# MCU_STM32F407ZGT6.net
KiCad netlist of a schematic drawn in Altium Designer
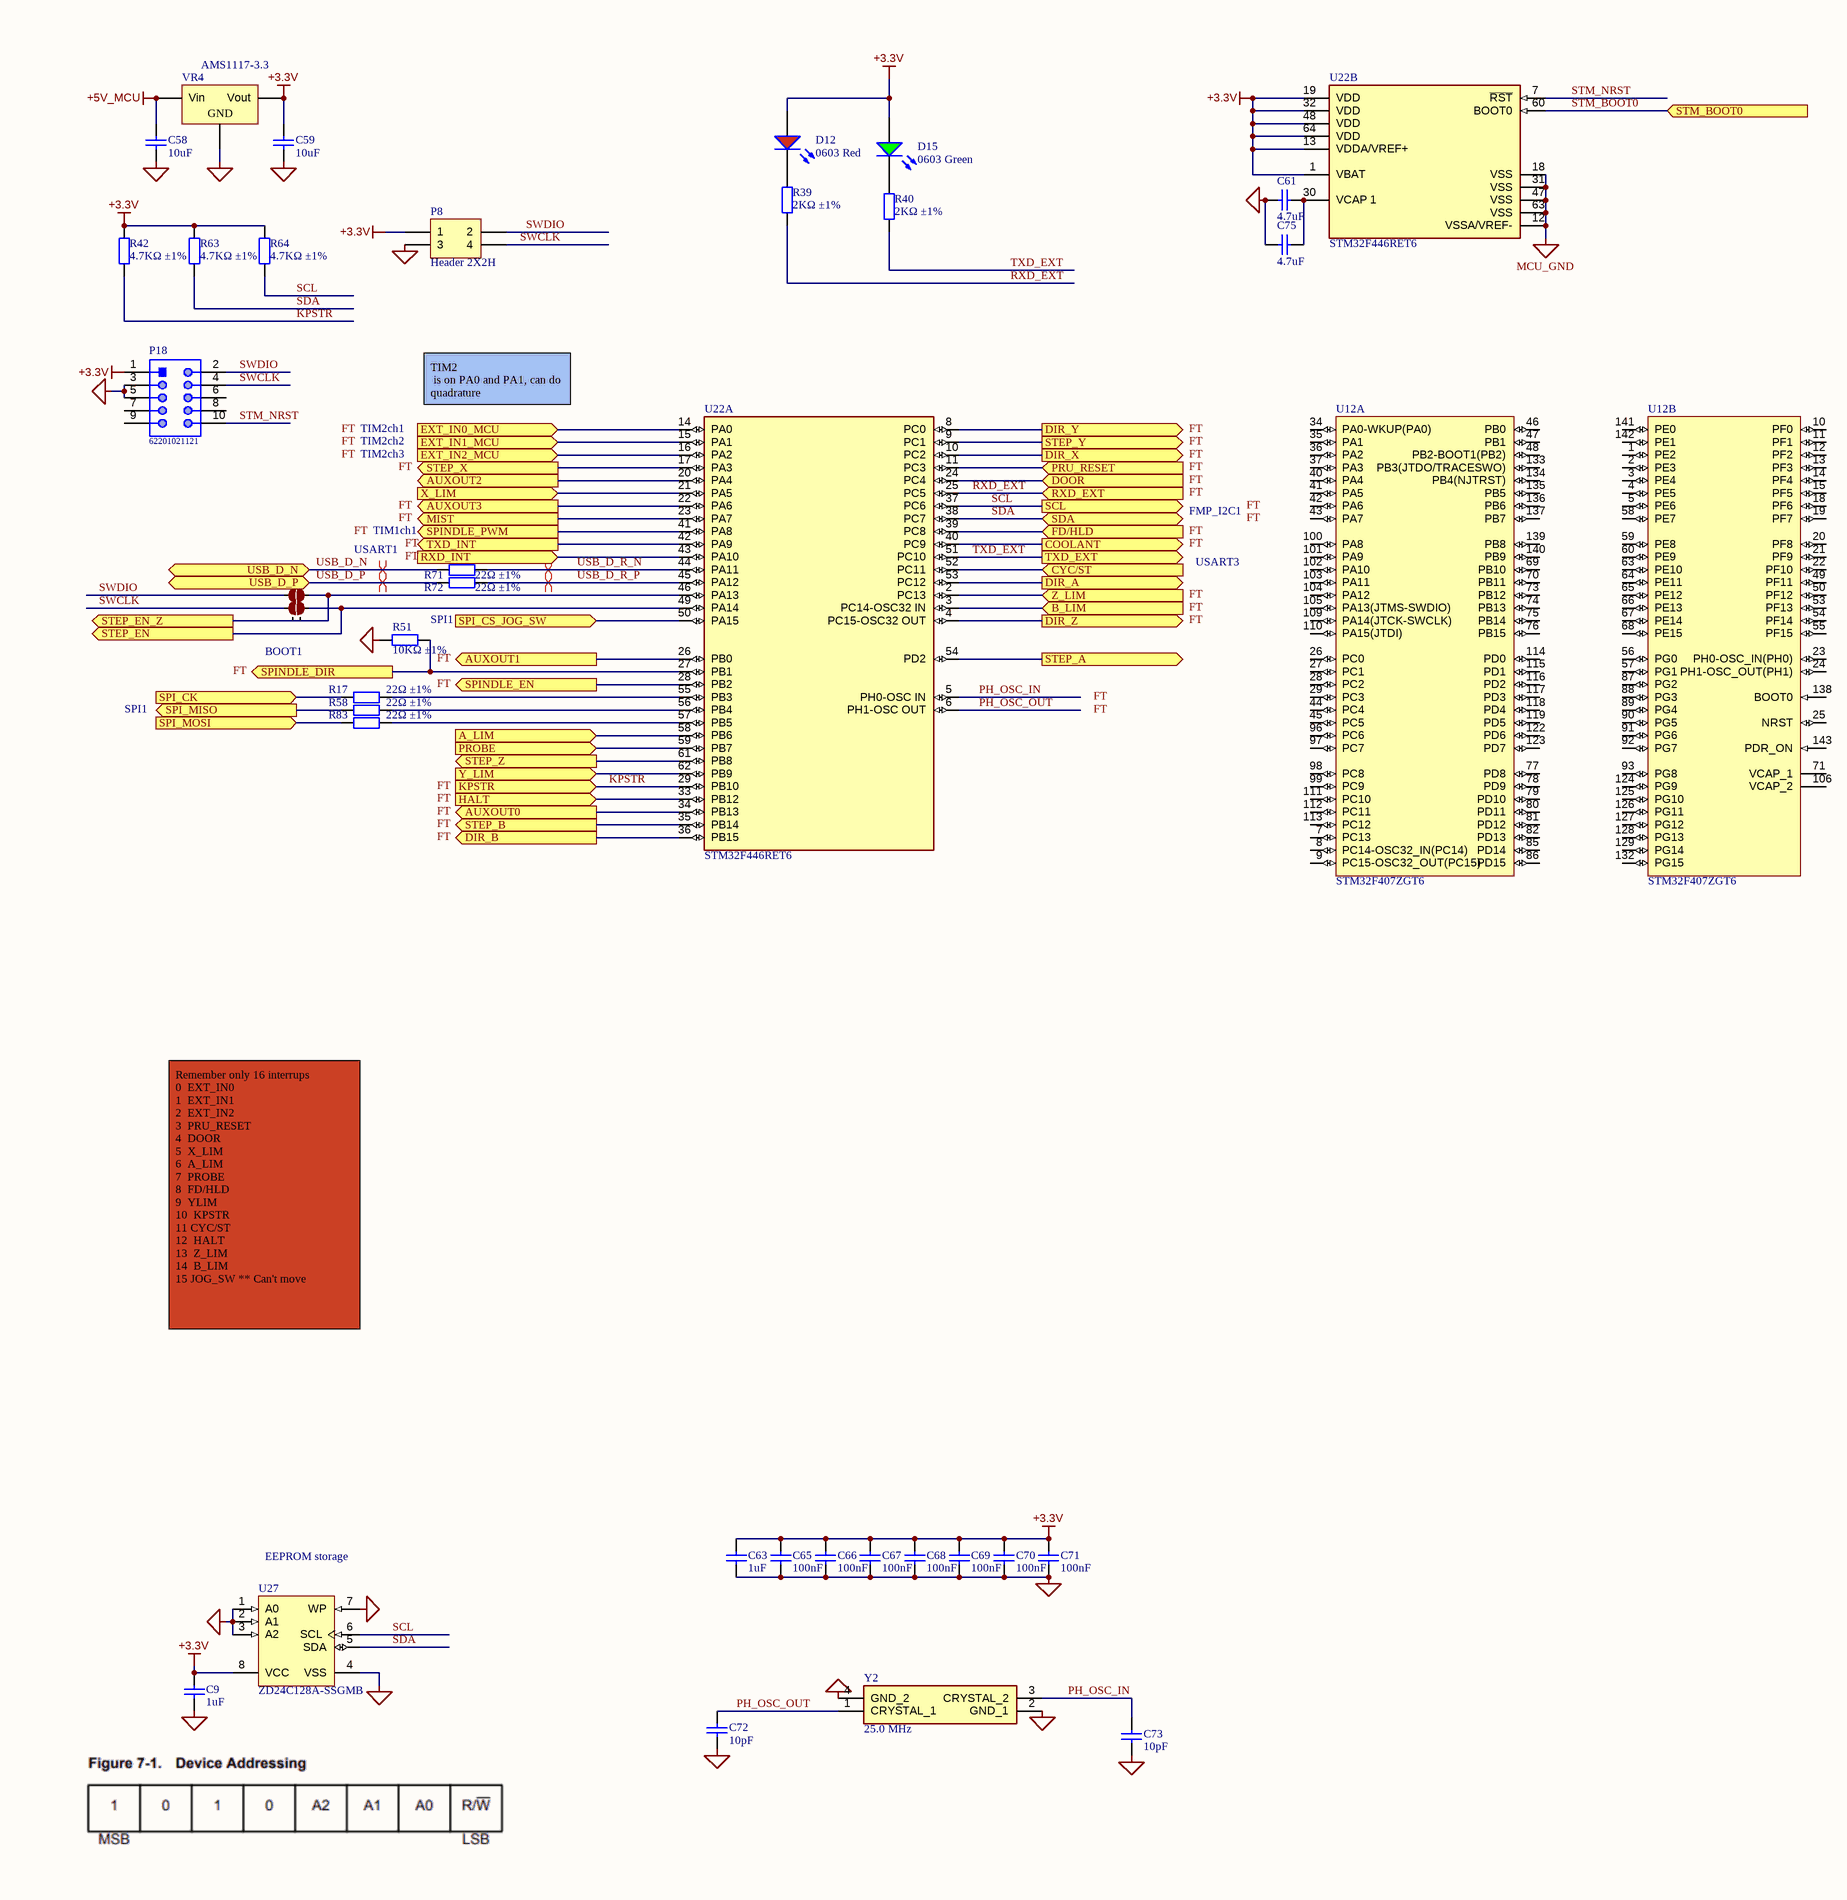
[diagram p0: MCU_STM32F407ZGT6.SchDoc, left]
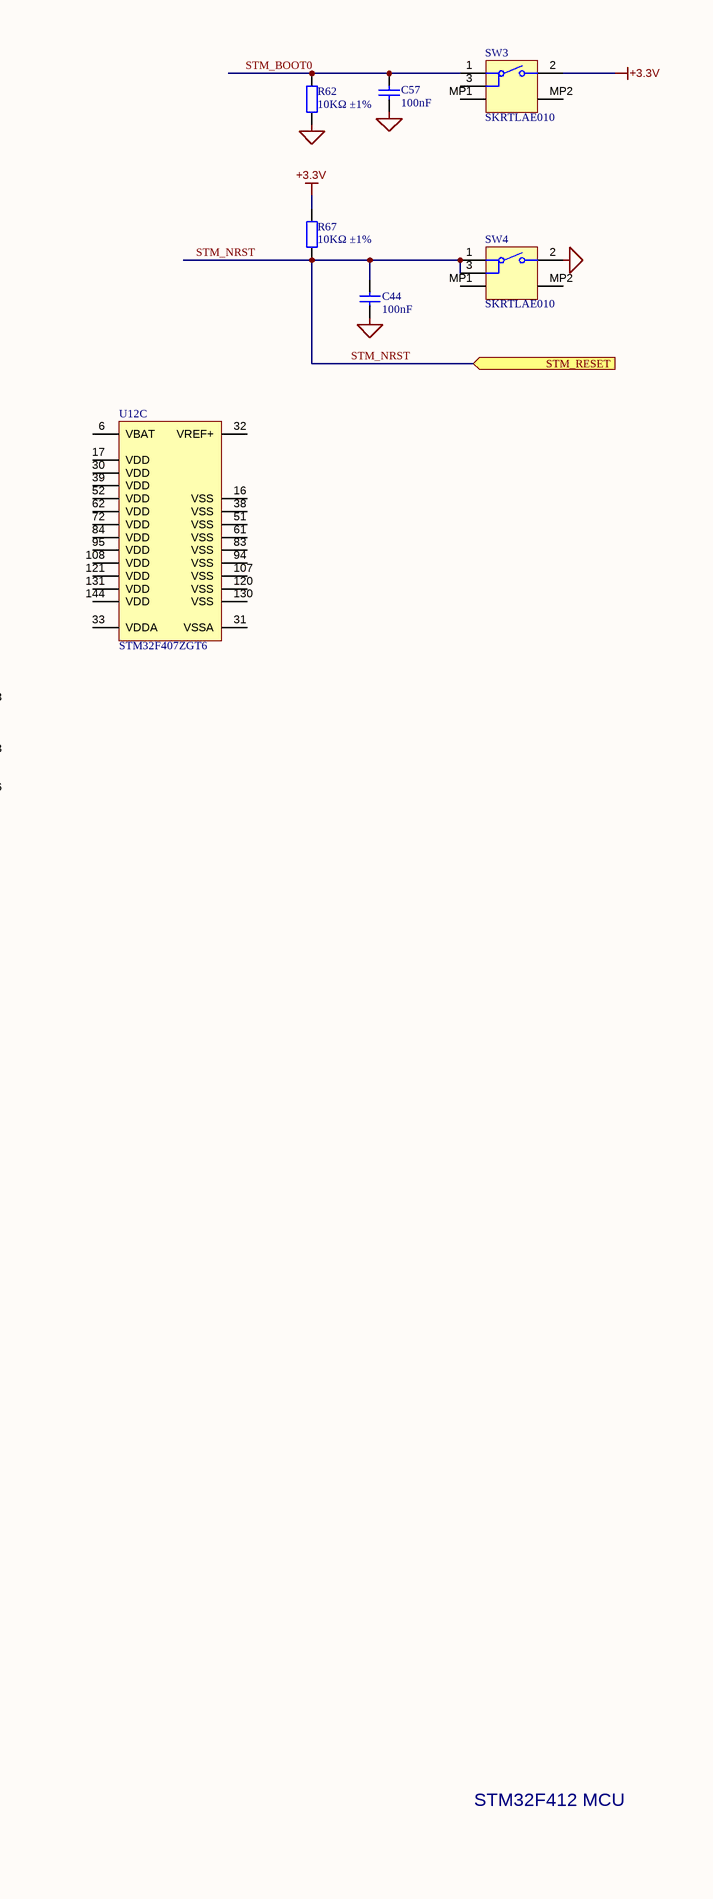
[diagram p1: MCU_STM32F407ZGT6.SchDoc, right]

(export (version "E")
  (design (tool "Eeschema 10.0.6"))
  (components
    (comp (ref "C9")
      (value "1uF")
      (footprint "0603_C")
      (description "Chip capacitors")
      (fields
        (field (name "MANUFACTURER") "Samsung Electro-Mechanics")
        (field (name "PARTNUMBER") "CL10A105KB8NNNC")
      )
      (libsource (lib "Cap") (part "0603 1uF (105) 10% 50V"))
    )
    (comp (ref "C44")
      (value "100nF")
      (footprint "0603_C")
      (description "Chip capacitors")
      (fields (field (name "MANUFACTURER") "YAGEO") (field (name "PARTNUMBER") "CC0603KRX7R9BB104"))
      (libsource (lib "Cap") (part "0603 100nF (104) 10% 50V"))
    )
    (comp (ref "C57")
      (value "100nF")
      (footprint "0603_C")
      (description "Chip capacitors")
      (fields (field (name "MANUFACTURER") "YAGEO") (field (name "PARTNUMBER") "CC0603KRX7R9BB104"))
      (libsource (lib "Cap") (part "0603 100nF (104) 10% 50V"))
    )
    (comp (ref "C58")
      (value "10uF")
      (footprint "1206_C")
      (description "Chip capacitors")
      (fields
        (field (name "MANUFACTURER") "Samsung Electro-Mechanics")
        (field (name "PARTNUMBER") "CL31A106KBHNNNE")
      )
      (libsource (lib "Cap") (part "1206 10uF (106) 10% 50V"))
    )
    (comp (ref "C59")
      (value "10uF")
      (footprint "1206_C")
      (description "Chip capacitors")
      (fields
        (field (name "MANUFACTURER") "Samsung Electro-Mechanics")
        (field (name "PARTNUMBER") "CL31A106KBHNNNE")
      )
      (libsource (lib "Cap") (part "1206 10uF (106) 10% 50V"))
    )
    (comp (ref "C61")
      (value "4.7uF")
      (footprint "0603_C")
      (description "Chip capacitors")
      (fields
        (field (name "MANUFACTURER") "Samsung Electro-Mechanics")
        (field (name "PARTNUMBER") "CL10A475KO8NNNC")
      )
      (libsource (lib "Cap") (part "0603 4.7uF (475) 10% 16V"))
    )
    (comp (ref "C63")
      (value "1uF")
      (footprint "0603_C")
      (description "Chip capacitors")
      (fields
        (field (name "MANUFACTURER") "Samsung Electro-Mechanics")
        (field (name "PARTNUMBER") "CL10A105KB8NNNC")
      )
      (libsource (lib "Cap") (part "0603 1uF (105) 10% 50V"))
    )
    (comp (ref "C65")
      (value "100nF")
      (footprint "0603_C")
      (description "Chip capacitors")
      (fields (field (name "MANUFACTURER") "YAGEO") (field (name "PARTNUMBER") "CC0603KRX7R9BB104"))
      (libsource (lib "Cap") (part "0603 100nF (104) 10% 50V"))
    )
    (comp (ref "C66")
      (value "100nF")
      (footprint "0603_C")
      (description "Chip capacitors")
      (fields (field (name "MANUFACTURER") "YAGEO") (field (name "PARTNUMBER") "CC0603KRX7R9BB104"))
      (libsource (lib "Cap") (part "0603 100nF (104) 10% 50V"))
    )
    (comp (ref "C67")
      (value "100nF")
      (footprint "0603_C")
      (description "Chip capacitors")
      (fields (field (name "MANUFACTURER") "YAGEO") (field (name "PARTNUMBER") "CC0603KRX7R9BB104"))
      (libsource (lib "Cap") (part "0603 100nF (104) 10% 50V"))
    )
    (comp (ref "C68")
      (value "100nF")
      (footprint "0603_C")
      (description "Chip capacitors")
      (fields (field (name "MANUFACTURER") "YAGEO") (field (name "PARTNUMBER") "CC0603KRX7R9BB104"))
      (libsource (lib "Cap") (part "0603 100nF (104) 10% 50V"))
    )
    (comp (ref "C69")
      (value "100nF")
      (footprint "0603_C")
      (description "Chip capacitors")
      (fields (field (name "MANUFACTURER") "YAGEO") (field (name "PARTNUMBER") "CC0603KRX7R9BB104"))
      (libsource (lib "Cap") (part "0603 100nF (104) 10% 50V"))
    )
    (comp (ref "C70")
      (value "100nF")
      (footprint "0603_C")
      (description "Chip capacitors")
      (fields (field (name "MANUFACTURER") "YAGEO") (field (name "PARTNUMBER") "CC0603KRX7R9BB104"))
      (libsource (lib "Cap") (part "0603 100nF (104) 10% 50V"))
    )
    (comp (ref "C71")
      (value "100nF")
      (footprint "0603_C")
      (description "Chip capacitors")
      (fields (field (name "MANUFACTURER") "YAGEO") (field (name "PARTNUMBER") "CC0603KRX7R9BB104"))
      (libsource (lib "Cap") (part "0603 100nF (104) 10% 50V"))
    )
    (comp (ref "C72")
      (value "10pF")
      (footprint "0603_C")
      (description "Chip capacitors")
      (fields
        (field (name "MANUFACTURER") "Samsung Electro-Mechanics")
        (field (name "PARTNUMBER") "CL10C100JB8NNNC")
      )
      (libsource (lib "Cap") (part "0603 10pF (100) 5% 50V"))
    )
    (comp (ref "C73")
      (value "10pF")
      (footprint "0603_C")
      (description "Chip capacitors")
      (fields
        (field (name "MANUFACTURER") "Samsung Electro-Mechanics")
        (field (name "PARTNUMBER") "CL10C100JB8NNNC")
      )
      (libsource (lib "Cap") (part "0603 10pF (100) 5% 50V"))
    )
    (comp (ref "C75")
      (value "4.7uF")
      (footprint "0603_C")
      (description "Chip capacitors")
      (fields
        (field (name "MANUFACTURER") "Samsung Electro-Mechanics")
        (field (name "PARTNUMBER") "CL10A475KO8NNNC")
      )
      (libsource (lib "Cap") (part "0603 4.7uF (475) 10% 16V"))
    )
    (comp (ref "D12")
      (value "0603 Red")
      (footprint "0603_LED_S1")
      (description "LED")
      (libsource (lib "LED") (part "0603 LED Red"))
    )
    (comp (ref "D15")
      (value "0603 Green")
      (footprint "0603_LED_S1")
      (description "LED")
      (libsource (lib "LED") (part "0603 LED Green"))
    )
    (comp (ref "J10")
      (value "2 way net solder junction - Normally Open")
      (footprint "2waySolder_NO")
      (libsource (lib "PrintNC_GRBLHAL_Breakout") (part "2waySolderNO"))
    )
    (comp (ref "J11")
      (value "2 way net solder junction - Normally Open")
      (footprint "2waySolder_NO")
      (libsource (lib "PrintNC_GRBLHAL_Breakout") (part "2waySolderNO"))
    )
    (comp (ref "P8")
      (value "Header 2X2H")
      (footprint "HDR2X2H")
      (description "Header, 2-Pin, Dual row, Right Angle")
      (fields (field (name "PUBLISHER") "Altium Limited"))
      (libsource (lib "Miscellaneous Connectors") (part "Header 2X2H"))
    )
    (comp (ref "P18")
      (value "62201021121")
      (footprint "62201021121")
      (description "THT Vertical Pin Header WR-PHD, Pitch 1.27 mm, Dual Row, 10 pins")
      (fields (field (name "MANUFACTURER") "Wurth Elektronik") (field (name "PUBLISHER") "WurthElektronik"))
      (libsource (lib "Altium Content Vault") (part "WE-CN-2P-M-R10"))
    )
    (comp (ref "R17")
      (value "22Ω ±1%")
      (footprint "0603_R")
      (description "Chip resistor")
      (fields (field (name "MANUFACTURER") "Uniroyal Elec") (field (name "PARTNUMBER") "0603WAF220JT5E"))
      (libsource (lib "RES") (part "0603 22R (22R0) 1%"))
    )
    (comp (ref "R39")
      (value "2KΩ ±1%")
      (footprint "0603_R")
      (description "Chip resistor")
      (fields (field (name "MANUFACTURER") "Uniroyal Elec") (field (name "PARTNUMBER") "0603WAF2001T5E"))
      (libsource (lib "RES") (part "0603 2K (2001) 1%"))
    )
    (comp (ref "R40")
      (value "2KΩ ±1%")
      (footprint "0603_R")
      (description "Chip resistor")
      (fields (field (name "MANUFACTURER") "Uniroyal Elec") (field (name "PARTNUMBER") "0603WAF2001T5E"))
      (libsource (lib "RES") (part "0603 2K (2001) 1%"))
    )
    (comp (ref "R42")
      (value "4.7KΩ ±1%")
      (footprint "0603_R")
      (description "Chip resistor")
      (fields (field (name "MANUFACTURER") "Uniroyal Elec") (field (name "PARTNUMBER") "0603WAF4701T5E"))
      (libsource (lib "RES") (part "0603 4.7K (4701) 1%"))
    )
    (comp (ref "R51")
      (value "10KΩ ±1%")
      (footprint "0603_R")
      (description "Chip resistor")
      (fields (field (name "MANUFACTURER") "Uniroyal Elec") (field (name "PARTNUMBER") "0603WAF1002T5E"))
      (libsource (lib "RES") (part "0603 10K (1002) 1%"))
    )
    (comp (ref "R58")
      (value "22Ω ±1%")
      (footprint "0603_R")
      (description "Chip resistor")
      (fields (field (name "MANUFACTURER") "Uniroyal Elec") (field (name "PARTNUMBER") "0603WAF220JT5E"))
      (libsource (lib "RES") (part "0603 22R (22R0) 1%"))
    )
    (comp (ref "R62")
      (value "10KΩ ±1%")
      (footprint "0603_R")
      (description "Chip resistor")
      (fields (field (name "MANUFACTURER") "Uniroyal Elec") (field (name "PARTNUMBER") "0603WAF1002T5E"))
      (libsource (lib "") (part "0603 10K (1002) 1%_1"))
    )
    (comp (ref "R63")
      (value "4.7KΩ ±1%")
      (footprint "0603_R")
      (description "Chip resistor")
      (fields (field (name "MANUFACTURER") "Uniroyal Elec") (field (name "PARTNUMBER") "0603WAF4701T5E"))
      (libsource (lib "RES") (part "0603 4.7K (4701) 1%"))
    )
    (comp (ref "R64")
      (value "4.7KΩ ±1%")
      (footprint "0603_R")
      (description "Chip resistor")
      (fields (field (name "MANUFACTURER") "Uniroyal Elec") (field (name "PARTNUMBER") "0603WAF4701T5E"))
      (libsource (lib "RES") (part "0603 4.7K (4701) 1%"))
    )
    (comp (ref "R67")
      (value "10KΩ ±1%")
      (footprint "0603_R")
      (description "Chip resistor")
      (fields (field (name "MANUFACTURER") "Uniroyal Elec") (field (name "PARTNUMBER") "0603WAF1002T5E"))
      (libsource (lib "") (part "0603 10K (1002) 1%_1"))
    )
    (comp (ref "R71")
      (value "22Ω ±1%")
      (footprint "0603_R")
      (description "Chip resistor")
      (fields (field (name "MANUFACTURER") "Uniroyal Elec") (field (name "PARTNUMBER") "0603WAF220JT5E"))
      (libsource (lib "RES") (part "0603 22R (22R0) 1%"))
    )
    (comp (ref "R72")
      (value "22Ω ±1%")
      (footprint "0603_R")
      (description "Chip resistor")
      (fields (field (name "MANUFACTURER") "Uniroyal Elec") (field (name "PARTNUMBER") "0603WAF220JT5E"))
      (libsource (lib "RES") (part "0603 22R (22R0) 1%"))
    )
    (comp (ref "R83")
      (value "22Ω ±1%")
      (footprint "0603_R")
      (description "Chip resistor")
      (fields (field (name "MANUFACTURER") "Uniroyal Elec") (field (name "PARTNUMBER") "0603WAF220JT5E"))
      (libsource (lib "RES") (part "0603 22R (22R0) 1%"))
    )
    (comp (ref "SW3")
      (value "SKRTLAE010")
      (footprint "ALPS-SKRTLAE010_V")
      (description "Side Push Type, 250 V, -40 to 90 degC, 3-Pin SMD, RoHS, Tape and Reel")
      (fields (field (name "MANUFACTURER") "ALPS"))
      (libsource (lib "Altium Content Vault") (part "SW_SPST-3_A"))
    )
    (comp (ref "SW4")
      (value "SKRTLAE010")
      (footprint "ALPS-SKRTLAE010_V")
      (description "Side Push Type, 250 V, -40 to 90 degC, 3-Pin SMD, RoHS, Tape and Reel")
      (fields (field (name "MANUFACTURER") "ALPS"))
      (libsource (lib "Altium Content Vault") (part "SW_SPST-3_A"))
    )
    (comp (ref "U12")
      (value "STM32F407ZGT6")
      (footprint "STM-LQFP144_L")
      (fields (field (name "MANUFACTURER") "STMicroelectronics") (field (name "PARTNUMBER") "STM32F407ZET6"))
      (libsource (lib "Universal_CNC_Breakout") (part "STM32F407ZGT6"))
    )
    (comp (ref "U22")
      (value "STM32F446RET6")
      (footprint "FP-LQFP64-5W-IPC_B")
      (description "IC MCU 32BIT 512KB FLASH 64LQFP")
      (fields
        (field (name "OCTOPART") "https://octopart.com/stm32f446ret6-stmicroelectronics-52642920")
        (field (name "MANUFACTURER") "STMicroelectronics")
      )
      (libsource (lib "Universal_CNC_Breakout") (part "STM32F446RET6"))
    )
    (comp (ref "U27")
      (value "ZD24C128A-SSGMB")
      (footprint "SOIC-SN8_L")
      (description "IC EEPROM 128KBIT I2C 8SOIC")
      (libsource (lib "PrintNC_GRBLHAL_Breakout") (part "MEM-SEEPROM-34AA02-IL8"))
    )
    (comp (ref "VR4")
      (value "AMS1117-3.3")
      (footprint "SOT-223")
      (description "Vout=3.3V 1A 72dB@(120Hz) (LDO)")
      (libsource (lib "LDO") (part "SOT-223 AMS1117-3.3"))
    )
    (comp (ref "Y2")
      (value "25.0 MHz")
      (footprint "SamacSys:YSX321SL")
      (description "Crystal or Oscillator")
      (fields (field (name "MANUFACTURER_PART_NUMBER") "X322525MSB4SI"))
      (libsource (lib "*") (part "YSX321SL"))
    )
  )
  (nets
    (net (code "1") (name "+3.3V") (class "Default")
      (node (ref "C59") (pin "2") (pinfunction "2_2") (pintype "passive"))
      (node (ref "C63") (pin "2") (pinfunction "2_2") (pintype "passive"))
      (node (ref "C65") (pin "2") (pinfunction "2_2") (pintype "passive"))
      (node (ref "C66") (pin "2") (pinfunction "2_2") (pintype "passive"))
      (node (ref "C67") (pin "2") (pinfunction "2_2") (pintype "passive"))
      (node (ref "C68") (pin "2") (pinfunction "2_2") (pintype "passive"))
      (node (ref "C69") (pin "2") (pinfunction "2_2") (pintype "passive"))
      (node (ref "C70") (pin "2") (pinfunction "2_2") (pintype "passive"))
      (node (ref "C71") (pin "2") (pinfunction "2_2") (pintype "passive"))
      (node (ref "C9") (pin "2") (pinfunction "2_2") (pintype "passive"))
      (node (ref "D12") (pin "A") (pinfunction "A_A") (pintype "passive"))
      (node (ref "D15") (pin "A") (pinfunction "A_A") (pintype "passive"))
      (node (ref "P18") (pin "1") (pinfunction "1_1") (pintype "passive"))
      (node (ref "P8") (pin "1") (pinfunction "1_1") (pintype "passive"))
      (node (ref "R42") (pin "2") (pinfunction "2_2") (pintype "passive"))
      (node (ref "R63") (pin "2") (pinfunction "2_2") (pintype "passive"))
      (node (ref "R64") (pin "2") (pinfunction "2_2") (pintype "passive"))
      (node (ref "R67") (pin "1") (pinfunction "1_1") (pintype "passive"))
      (node (ref "SW3") (pin "2") (pinfunction "2_2") (pintype "passive"))
      (node (ref "U22") (pin "1") (pinfunction "VBAT_1") (pintype "power_in"))
      (node (ref "U22") (pin "13") (pinfunction "VDDA/VREF+_13") (pintype "power_in"))
      (node (ref "U22") (pin "19") (pinfunction "VDD_19") (pintype "power_in"))
      (node (ref "U22") (pin "32") (pinfunction "VDD_32") (pintype "power_in"))
      (node (ref "U22") (pin "48") (pinfunction "VDD_48") (pintype "power_in"))
      (node (ref "U22") (pin "64") (pinfunction "VDD_64") (pintype "power_in"))
      (node (ref "U27") (pin "8") (pinfunction "VCC_8") (pintype "power_in"))
      (node (ref "VR4") (pin "2") (pinfunction "Vout_2") (pintype "passive"))
    )
    (net (code "2") (name "+5V_MCU") (class "Default")
      (node (ref "C58") (pin "2") (pinfunction "2_2") (pintype "passive"))
      (node (ref "VR4") (pin "3") (pinfunction "Vin_3") (pintype "passive"))
    )
    (net (code "3") (name "/AUXOUT0") (class "Default")
      (node (ref "U22") (pin "34") (pinfunction "PB13_34") (pintype "bidirectional"))
    )
    (net (code "4") (name "/AUXOUT1") (class "Default")
      (node (ref "U22") (pin "26") (pinfunction "PB0_26") (pintype "bidirectional"))
    )
    (net (code "5") (name "/AUXOUT2") (class "Default")
      (node (ref "U22") (pin "20") (pinfunction "PA4_20") (pintype "bidirectional"))
    )
    (net (code "6") (name "/AUXOUT3") (class "Default")
      (node (ref "U22") (pin "22") (pinfunction "PA6_22") (pintype "bidirectional"))
    )
    (net (code "7") (name "/A_LIM") (class "Default")
      (node (ref "U22") (pin "58") (pinfunction "PB6_58") (pintype "bidirectional"))
    )
    (net (code "8") (name "/B_LIM") (class "Default")
      (node (ref "U22") (pin "3") (pinfunction "PC14-OSC32_IN_3") (pintype "bidirectional"))
    )
    (net (code "9") (name "/COOLANT") (class "Default")
      (node (ref "U22") (pin "40") (pinfunction "PC9_40") (pintype "bidirectional"))
    )
    (net (code "10") (name "/CYC{slash}ST") (class "Default")
      (node (ref "U22") (pin "52") (pinfunction "PC11_52") (pintype "bidirectional"))
    )
    (net (code "11") (name "/DIR_A") (class "Default")
      (node (ref "U22") (pin "53") (pinfunction "PC12_53") (pintype "bidirectional"))
    )
    (net (code "12") (name "/DIR_B") (class "Default")
      (node (ref "U22") (pin "36") (pinfunction "PB15_36") (pintype "bidirectional"))
    )
    (net (code "13") (name "/DIR_X") (class "Default")
      (node (ref "U22") (pin "10") (pinfunction "PC2_10") (pintype "bidirectional"))
    )
    (net (code "14") (name "/DIR_Y") (class "Default")
      (node (ref "U22") (pin "8") (pinfunction "PC0_8") (pintype "bidirectional"))
    )
    (net (code "15") (name "/DIR_Z") (class "Default")
      (node (ref "U22") (pin "4") (pinfunction "PC15-OSC32_OUT_4") (pintype "bidirectional"))
    )
    (net (code "16") (name "/DOOR") (class "Default")
      (node (ref "U22") (pin "24") (pinfunction "PC4_24") (pintype "bidirectional"))
    )
    (net (code "17") (name "/EXT_IN0_MCU") (class "Default")
      (node (ref "U22") (pin "14") (pinfunction "PA0_14") (pintype "bidirectional"))
    )
    (net (code "18") (name "/EXT_IN1_MCU") (class "Default")
      (node (ref "U22") (pin "15") (pinfunction "PA1_15") (pintype "bidirectional"))
    )
    (net (code "19") (name "/EXT_IN2_MCU") (class "Default")
      (node (ref "U22") (pin "16") (pinfunction "PA2_16") (pintype "bidirectional"))
    )
    (net (code "20") (name "/FD{slash}HLD") (class "Default")
      (node (ref "U22") (pin "39") (pinfunction "PC8_39") (pintype "bidirectional"))
    )
    (net (code "21") (name "/HALT") (class "Default")
      (node (ref "U22") (pin "33") (pinfunction "PB12_33") (pintype "bidirectional"))
    )
    (net (code "22") (name "/KPSTR") (class "Default")
      (node (ref "R42") (pin "1") (pinfunction "1_1") (pintype "passive"))
      (node (ref "U22") (pin "29") (pinfunction "PB10_29") (pintype "bidirectional"))
    )
    (net (code "23") (name "/MIST") (class "Default")
      (node (ref "U22") (pin "23") (pinfunction "PA7_23") (pintype "bidirectional"))
    )
    (net (code "24") (name "/PH_OSC_IN") (class "Default")
      (node (ref "C73") (pin "2") (pinfunction "2_2") (pintype "passive"))
      (node (ref "U22") (pin "5") (pinfunction "PH0-OSC_IN_5") (pintype "bidirectional"))
      (node (ref "Y2") (pin "3") (pinfunction "CRYSTAL_2_3") (pintype "passive"))
    )
    (net (code "25") (name "/PH_OSC_OUT") (class "Default")
      (node (ref "C72") (pin "2") (pinfunction "2_2") (pintype "passive"))
      (node (ref "U22") (pin "6") (pinfunction "PH1-OSC_OUT_6") (pintype "bidirectional"))
      (node (ref "Y2") (pin "1") (pinfunction "CRYSTAL_1_1") (pintype "passive"))
    )
    (net (code "26") (name "/PROBE") (class "Default")
      (node (ref "U22") (pin "59") (pinfunction "PB7_59") (pintype "bidirectional"))
    )
    (net (code "27") (name "/PRU_RESET") (class "Default")
      (node (ref "U22") (pin "11") (pinfunction "PC3_11") (pintype "bidirectional"))
    )
    (net (code "28") (name "/RXD_EXT") (class "Default")
      (node (ref "R39") (pin "1") (pinfunction "1_1") (pintype "passive"))
      (node (ref "U22") (pin "25") (pinfunction "PC5_25") (pintype "bidirectional"))
    )
    (net (code "29") (name "/RXD_INT") (class "Default")
      (node (ref "U22") (pin "43") (pinfunction "PA10_43") (pintype "bidirectional"))
    )
    (net (code "30") (name "/SCL") (class "Default")
      (node (ref "R64") (pin "1") (pinfunction "1_1") (pintype "passive"))
      (node (ref "U22") (pin "37") (pinfunction "PC6_37") (pintype "bidirectional"))
      (node (ref "U27") (pin "6") (pinfunction "SCL_6") (pintype "input"))
    )
    (net (code "31") (name "/SDA") (class "Default")
      (node (ref "R63") (pin "1") (pinfunction "1_1") (pintype "passive"))
      (node (ref "U22") (pin "38") (pinfunction "PC7_38") (pintype "bidirectional"))
      (node (ref "U27") (pin "5") (pinfunction "SDA_5") (pintype "bidirectional"))
    )
    (net (code "32") (name "/SPINDLE_DIR") (class "Default")
      (node (ref "R51") (pin "2") (pinfunction "2_2") (pintype "passive"))
      (node (ref "U22") (pin "27") (pinfunction "PB1_27") (pintype "bidirectional"))
    )
    (net (code "33") (name "/SPINDLE_EN") (class "Default")
      (node (ref "U22") (pin "28") (pinfunction "PB2_28") (pintype "bidirectional"))
    )
    (net (code "34") (name "/SPINDLE_PWM") (class "Default")
      (node (ref "U22") (pin "41") (pinfunction "PA8_41") (pintype "bidirectional"))
    )
    (net (code "35") (name "/SPI_CK") (class "Default")
      (node (ref "R17") (pin "2") (pinfunction "2_2") (pintype "passive"))
    )
    (net (code "36") (name "/SPI_CS_JOG_SW") (class "Default")
      (node (ref "U22") (pin "50") (pinfunction "PA15_50") (pintype "bidirectional"))
    )
    (net (code "37") (name "/SPI_MISO") (class "Default")
      (node (ref "R58") (pin "2") (pinfunction "2_2") (pintype "passive"))
    )
    (net (code "38") (name "/SPI_MOSI") (class "Default")
      (node (ref "R83") (pin "2") (pinfunction "2_2") (pintype "passive"))
    )
    (net (code "39") (name "/STEP_A") (class "Default")
      (node (ref "U22") (pin "54") (pinfunction "PD2_54") (pintype "bidirectional"))
    )
    (net (code "40") (name "/STEP_B") (class "Default")
      (node (ref "U22") (pin "35") (pinfunction "PB14_35") (pintype "bidirectional"))
    )
    (net (code "41") (name "/STEP_EN") (class "Default")
      (node (ref "J11") (pin "2") (pinfunction "2_2") (pintype "passive"))
      (node (ref "U22") (pin "49") (pinfunction "PA14_49") (pintype "bidirectional"))
    )
    (net (code "42") (name "/STEP_EN_Z") (class "Default")
      (node (ref "J10") (pin "2") (pinfunction "2_2") (pintype "passive"))
      (node (ref "U22") (pin "46") (pinfunction "PA13_46") (pintype "bidirectional"))
    )
    (net (code "43") (name "/STEP_X") (class "Default")
      (node (ref "U22") (pin "17") (pinfunction "PA3_17") (pintype "bidirectional"))
    )
    (net (code "44") (name "/STEP_Y") (class "Default")
      (node (ref "U22") (pin "9") (pinfunction "PC1_9") (pintype "bidirectional"))
    )
    (net (code "45") (name "/STEP_Z") (class "Default")
      (node (ref "U22") (pin "61") (pinfunction "PB8_61") (pintype "bidirectional"))
    )
    (net (code "46") (name "/STM_BOOT0") (class "Default")
      (node (ref "C57") (pin "2") (pinfunction "2_2") (pintype "passive"))
      (node (ref "R62") (pin "1") (pinfunction "1_1") (pintype "passive"))
      (node (ref "SW3") (pin "1") (pinfunction "1_1") (pintype "passive"))
      (node (ref "U22") (pin "60") (pinfunction "BOOT0_60") (pintype "input"))
    )
    (net (code "47") (name "/STM_NRST") (class "Default")
      (node (ref "C44") (pin "2") (pinfunction "2_2") (pintype "passive"))
      (node (ref "P18") (pin "10") (pinfunction "10_10") (pintype "passive"))
      (node (ref "R67") (pin "2") (pinfunction "2_2") (pintype "passive"))
      (node (ref "SW4") (pin "1") (pinfunction "1_1") (pintype "passive"))
      (node (ref "SW4") (pin "3") (pinfunction "3_3") (pintype "passive"))
      (node (ref "U22") (pin "7") (pinfunction "~{RST}_7") (pintype "input"))
    )
    (net (code "48") (name "/SWCLK") (class "Default")
      (node (ref "J11") (pin "1") (pinfunction "1_1") (pintype "passive"))
      (node (ref "P18") (pin "4") (pinfunction "4_4") (pintype "passive"))
      (node (ref "P8") (pin "4") (pinfunction "4_4") (pintype "passive"))
    )
    (net (code "49") (name "/SWDIO") (class "Default")
      (node (ref "J10") (pin "1") (pinfunction "1_1") (pintype "passive"))
      (node (ref "P18") (pin "2") (pinfunction "2_2") (pintype "passive"))
      (node (ref "P8") (pin "2") (pinfunction "2_2") (pintype "passive"))
    )
    (net (code "50") (name "/TXD_EXT") (class "Default")
      (node (ref "R40") (pin "1") (pinfunction "1_1") (pintype "passive"))
      (node (ref "U22") (pin "51") (pinfunction "PC10_51") (pintype "bidirectional"))
    )
    (net (code "51") (name "/TXD_INT") (class "Default")
      (node (ref "U22") (pin "42") (pinfunction "PA9_42") (pintype "bidirectional"))
    )
    (net (code "52") (name "/USB_D_N") (class "Default")
      (node (ref "R71") (pin "2") (pinfunction "2_2") (pintype "passive"))
    )
    (net (code "53") (name "/USB_D_P") (class "Default")
      (node (ref "R72") (pin "2") (pinfunction "2_2") (pintype "passive"))
    )
    (net (code "54") (name "/USB_D_R_N") (class "Default")
      (node (ref "R71") (pin "1") (pinfunction "1_1") (pintype "passive"))
      (node (ref "U22") (pin "44") (pinfunction "PA11_44") (pintype "bidirectional"))
    )
    (net (code "55") (name "/USB_D_R_P") (class "Default")
      (node (ref "R72") (pin "1") (pinfunction "1_1") (pintype "passive"))
      (node (ref "U22") (pin "45") (pinfunction "PA12_45") (pintype "bidirectional"))
    )
    (net (code "56") (name "/X_LIM") (class "Default")
      (node (ref "U22") (pin "21") (pinfunction "PA5_21") (pintype "bidirectional"))
    )
    (net (code "57") (name "/Y_LIM") (class "Default")
      (node (ref "U22") (pin "62") (pinfunction "PB9_62") (pintype "bidirectional"))
    )
    (net (code "58") (name "/Z_LIM") (class "Default")
      (node (ref "U22") (pin "2") (pinfunction "PC13_2") (pintype "bidirectional"))
    )
    (net (code "59") (name "MCU_GND") (class "Default")
      (node (ref "C44") (pin "1") (pinfunction "1_1") (pintype "passive"))
      (node (ref "C57") (pin "1") (pinfunction "1_1") (pintype "passive"))
      (node (ref "C58") (pin "1") (pinfunction "1_1") (pintype "passive"))
      (node (ref "C59") (pin "1") (pinfunction "1_1") (pintype "passive"))
      (node (ref "C61") (pin "1") (pinfunction "1_1") (pintype "passive"))
      (node (ref "C63") (pin "1") (pinfunction "1_1") (pintype "passive"))
      (node (ref "C65") (pin "1") (pinfunction "1_1") (pintype "passive"))
      (node (ref "C66") (pin "1") (pinfunction "1_1") (pintype "passive"))
      (node (ref "C67") (pin "1") (pinfunction "1_1") (pintype "passive"))
      (node (ref "C68") (pin "1") (pinfunction "1_1") (pintype "passive"))
      (node (ref "C69") (pin "1") (pinfunction "1_1") (pintype "passive"))
      (node (ref "C70") (pin "1") (pinfunction "1_1") (pintype "passive"))
      (node (ref "C71") (pin "1") (pinfunction "1_1") (pintype "passive"))
      (node (ref "C72") (pin "1") (pinfunction "1_1") (pintype "passive"))
      (node (ref "C73") (pin "1") (pinfunction "1_1") (pintype "passive"))
      (node (ref "C75") (pin "1") (pinfunction "1_1") (pintype "passive"))
      (node (ref "C9") (pin "1") (pinfunction "1_1") (pintype "passive"))
      (node (ref "P18") (pin "3") (pinfunction "3_3") (pintype "passive"))
      (node (ref "P18") (pin "5") (pinfunction "5_5") (pintype "passive"))
      (node (ref "P8") (pin "3") (pinfunction "3_3") (pintype "passive"))
      (node (ref "R51") (pin "1") (pinfunction "1_1") (pintype "passive"))
      (node (ref "R62") (pin "2") (pinfunction "2_2") (pintype "passive"))
      (node (ref "SW4") (pin "2") (pinfunction "2_2") (pintype "passive"))
      (node (ref "U22") (pin "12") (pinfunction "VSSA/VREF-_12") (pintype "power_in"))
      (node (ref "U22") (pin "18") (pinfunction "VSS_18") (pintype "power_in"))
      (node (ref "U22") (pin "31") (pinfunction "VSS_31") (pintype "power_in"))
      (node (ref "U22") (pin "47") (pinfunction "VSS_47") (pintype "power_in"))
      (node (ref "U22") (pin "63") (pinfunction "VSS_63") (pintype "power_in"))
      (node (ref "U27") (pin "1") (pinfunction "A0_1") (pintype "input"))
      (node (ref "U27") (pin "2") (pinfunction "A1_2") (pintype "input"))
      (node (ref "U27") (pin "3") (pinfunction "A2_3") (pintype "input"))
      (node (ref "U27") (pin "4") (pinfunction "VSS_4") (pintype "power_in"))
      (node (ref "U27") (pin "7") (pinfunction "WP_7") (pintype "input"))
      (node (ref "VR4") (pin "1") (pinfunction "GND_1") (pintype "passive"))
      (node (ref "Y2") (pin "2") (pinfunction "GND_1_2") (pintype "passive"))
      (node (ref "Y2") (pin "4") (pinfunction "GND_2_4") (pintype "passive"))
    )
    (net (code "60") (name "Net-(D12-PadK)") (class "Default")
      (node (ref "D12") (pin "K") (pinfunction "K_K") (pintype "passive"))
      (node (ref "R39") (pin "2") (pinfunction "2_2") (pintype "passive"))
    )
    (net (code "61") (name "Net-(D15-PadK)") (class "Default")
      (node (ref "D15") (pin "K") (pinfunction "K_K") (pintype "passive"))
      (node (ref "R40") (pin "2") (pinfunction "2_2") (pintype "passive"))
    )
    (net (code "62") (name "Net-(U22A-PB3)") (class "Default")
      (node (ref "R17") (pin "1") (pinfunction "1_1") (pintype "passive"))
      (node (ref "U22") (pin "55") (pinfunction "PB3_55") (pintype "bidirectional"))
    )
    (net (code "63") (name "Net-(U22A-PB4)") (class "Default")
      (node (ref "R58") (pin "1") (pinfunction "1_1") (pintype "passive"))
      (node (ref "U22") (pin "56") (pinfunction "PB4_56") (pintype "bidirectional"))
    )
    (net (code "64") (name "Net-(U22A-PB5)") (class "Default")
      (node (ref "R83") (pin "1") (pinfunction "1_1") (pintype "passive"))
      (node (ref "U22") (pin "57") (pinfunction "PB5_57") (pintype "bidirectional"))
    )
    (net (code "65") (name "Net-(U22B-VCAP_1)") (class "Default")
      (node (ref "C61") (pin "2") (pinfunction "2_2") (pintype "passive"))
      (node (ref "C75") (pin "2") (pinfunction "2_2") (pintype "passive"))
      (node (ref "U22") (pin "30") (pinfunction "VCAP_1_30") (pintype "power_in"))
    )
    (net (code "66") (name "unconnected-(P18-Pad6)") (class "Default")
      (node (ref "P18") (pin "6") (pinfunction "6_6") (pintype "passive"))
    )
    (net (code "67") (name "unconnected-(P18-Pad7)") (class "Default")
      (node (ref "P18") (pin "7") (pinfunction "7_7") (pintype "passive"))
    )
    (net (code "68") (name "unconnected-(P18-Pad8)") (class "Default")
      (node (ref "P18") (pin "8") (pinfunction "8_8") (pintype "passive"))
    )
    (net (code "69") (name "unconnected-(P18-Pad9)") (class "Default")
      (node (ref "P18") (pin "9") (pinfunction "9_9") (pintype "passive"))
    )
    (net (code "70") (name "unconnected-(SW3-Pad3)") (class "Default")
      (node (ref "SW3") (pin "3") (pinfunction "3_3") (pintype "passive"))
    )
    (net (code "71") (name "unconnected-(SW3-PadMP1)") (class "Default")
      (node (ref "SW3") (pin "MP1") (pinfunction "MP1_MP1") (pintype "passive"))
    )
    (net (code "72") (name "unconnected-(SW3-PadMP2)") (class "Default")
      (node (ref "SW3") (pin "MP2") (pinfunction "MP2_MP2") (pintype "passive"))
    )
    (net (code "73") (name "unconnected-(SW4-PadMP1)") (class "Default")
      (node (ref "SW4") (pin "MP1") (pinfunction "MP1_MP1") (pintype "passive"))
    )
    (net (code "74") (name "unconnected-(SW4-PadMP2)") (class "Default")
      (node (ref "SW4") (pin "MP2") (pinfunction "MP2_MP2") (pintype "passive"))
    )
    (net (code "75") (name "unconnected-(U12A-PA0-WKUP(PA0)-Pad34)") (class "Default")
      (node (ref "U12") (pin "34") (pinfunction "PA0-WKUP(PA0)_34") (pintype "bidirectional"))
    )
    (net (code "76") (name "unconnected-(U12A-PA1-Pad35)") (class "Default")
      (node (ref "U12") (pin "35") (pinfunction "PA1_35") (pintype "bidirectional"))
    )
    (net (code "77") (name "unconnected-(U12A-PA2-Pad36)") (class "Default")
      (node (ref "U12") (pin "36") (pinfunction "PA2_36") (pintype "bidirectional"))
    )
    (net (code "78") (name "unconnected-(U12A-PA3-Pad37)") (class "Default")
      (node (ref "U12") (pin "37") (pinfunction "PA3_37") (pintype "bidirectional"))
    )
    (net (code "79") (name "unconnected-(U12A-PA4-Pad40)") (class "Default")
      (node (ref "U12") (pin "40") (pinfunction "PA4_40") (pintype "bidirectional"))
    )
    (net (code "80") (name "unconnected-(U12A-PA5-Pad41)") (class "Default")
      (node (ref "U12") (pin "41") (pinfunction "PA5_41") (pintype "bidirectional"))
    )
    (net (code "81") (name "unconnected-(U12A-PA6-Pad42)") (class "Default")
      (node (ref "U12") (pin "42") (pinfunction "PA6_42") (pintype "bidirectional"))
    )
    (net (code "82") (name "unconnected-(U12A-PA7-Pad43)") (class "Default")
      (node (ref "U12") (pin "43") (pinfunction "PA7_43") (pintype "bidirectional"))
    )
    (net (code "83") (name "unconnected-(U12A-PA8-Pad100)") (class "Default")
      (node (ref "U12") (pin "100") (pinfunction "PA8_100") (pintype "bidirectional"))
    )
    (net (code "84") (name "unconnected-(U12A-PA9-Pad101)") (class "Default")
      (node (ref "U12") (pin "101") (pinfunction "PA9_101") (pintype "bidirectional"))
    )
    (net (code "85") (name "unconnected-(U12A-PA10-Pad102)") (class "Default")
      (node (ref "U12") (pin "102") (pinfunction "PA10_102") (pintype "bidirectional"))
    )
    (net (code "86") (name "unconnected-(U12A-PA11-Pad103)") (class "Default")
      (node (ref "U12") (pin "103") (pinfunction "PA11_103") (pintype "bidirectional"))
    )
    (net (code "87") (name "unconnected-(U12A-PA12-Pad104)") (class "Default")
      (node (ref "U12") (pin "104") (pinfunction "PA12_104") (pintype "bidirectional"))
    )
    (net (code "88") (name "unconnected-(U12A-PA13(JTMS-SWDIO)-Pad105)") (class "Default")
      (node (ref "U12") (pin "105") (pinfunction "PA13(JTMS-SWDIO)_105") (pintype "bidirectional"))
    )
    (net (code "89") (name "unconnected-(U12A-PA14(JTCK-SWCLK)-Pad109)") (class "Default")
      (node (ref "U12") (pin "109") (pinfunction "PA14(JTCK-SWCLK)_109") (pintype "bidirectional"))
    )
    (net (code "90") (name "unconnected-(U12A-PA15(JTDI)-Pad110)") (class "Default")
      (node (ref "U12") (pin "110") (pinfunction "PA15(JTDI)_110") (pintype "bidirectional"))
    )
    (net (code "91") (name "unconnected-(U12A-PB0-Pad46)") (class "Default")
      (node (ref "U12") (pin "46") (pinfunction "PB0_46") (pintype "bidirectional"))
    )
    (net (code "92") (name "unconnected-(U12A-PB1-Pad47)") (class "Default")
      (node (ref "U12") (pin "47") (pinfunction "PB1_47") (pintype "bidirectional"))
    )
    (net (code "93") (name "unconnected-(U12A-PB2-BOOT1(PB2)-Pad48)") (class "Default")
      (node (ref "U12") (pin "48") (pinfunction "PB2-BOOT1(PB2)_48") (pintype "bidirectional"))
    )
    (net (code "94") (name "unconnected-(U12A-PB3(JTDO{slash}TRACESWO)-Pad133)") (class "Default")
      (node (ref "U12") (pin "133") (pinfunction "PB3(JTDO/TRACESWO)_133") (pintype "bidirectional"))
    )
    (net (code "95") (name "unconnected-(U12A-PB4(NJTRST)-Pad134)") (class "Default")
      (node (ref "U12") (pin "134") (pinfunction "PB4(NJTRST)_134") (pintype "bidirectional"))
    )
    (net (code "96") (name "unconnected-(U12A-PB5-Pad135)") (class "Default")
      (node (ref "U12") (pin "135") (pinfunction "PB5_135") (pintype "bidirectional"))
    )
    (net (code "97") (name "unconnected-(U12A-PB6-Pad136)") (class "Default")
      (node (ref "U12") (pin "136") (pinfunction "PB6_136") (pintype "bidirectional"))
    )
    (net (code "98") (name "unconnected-(U12A-PB7-Pad137)") (class "Default")
      (node (ref "U12") (pin "137") (pinfunction "PB7_137") (pintype "bidirectional"))
    )
    (net (code "99") (name "unconnected-(U12A-PB8-Pad139)") (class "Default")
      (node (ref "U12") (pin "139") (pinfunction "PB8_139") (pintype "bidirectional"))
    )
    (net (code "100") (name "unconnected-(U12A-PB9-Pad140)") (class "Default")
      (node (ref "U12") (pin "140") (pinfunction "PB9_140") (pintype "bidirectional"))
    )
    (net (code "101") (name "unconnected-(U12A-PB10-Pad69)") (class "Default")
      (node (ref "U12") (pin "69") (pinfunction "PB10_69") (pintype "bidirectional"))
    )
    (net (code "102") (name "unconnected-(U12A-PB11-Pad70)") (class "Default")
      (node (ref "U12") (pin "70") (pinfunction "PB11_70") (pintype "bidirectional"))
    )
    (net (code "103") (name "unconnected-(U12A-PB12-Pad73)") (class "Default")
      (node (ref "U12") (pin "73") (pinfunction "PB12_73") (pintype "bidirectional"))
    )
    (net (code "104") (name "unconnected-(U12A-PB13-Pad74)") (class "Default")
      (node (ref "U12") (pin "74") (pinfunction "PB13_74") (pintype "bidirectional"))
    )
    (net (code "105") (name "unconnected-(U12A-PB14-Pad75)") (class "Default")
      (node (ref "U12") (pin "75") (pinfunction "PB14_75") (pintype "bidirectional"))
    )
    (net (code "106") (name "unconnected-(U12A-PB15-Pad76)") (class "Default")
      (node (ref "U12") (pin "76") (pinfunction "PB15_76") (pintype "bidirectional"))
    )
    (net (code "107") (name "unconnected-(U12A-PC0-Pad26)") (class "Default")
      (node (ref "U12") (pin "26") (pinfunction "PC0_26") (pintype "bidirectional"))
    )
    (net (code "108") (name "unconnected-(U12A-PC1-Pad27)") (class "Default")
      (node (ref "U12") (pin "27") (pinfunction "PC1_27") (pintype "bidirectional"))
    )
    (net (code "109") (name "unconnected-(U12A-PC2-Pad28)") (class "Default")
      (node (ref "U12") (pin "28") (pinfunction "PC2_28") (pintype "bidirectional"))
    )
    (net (code "110") (name "unconnected-(U12A-PC3-Pad29)") (class "Default")
      (node (ref "U12") (pin "29") (pinfunction "PC3_29") (pintype "bidirectional"))
    )
    (net (code "111") (name "unconnected-(U12A-PC4-Pad44)") (class "Default")
      (node (ref "U12") (pin "44") (pinfunction "PC4_44") (pintype "bidirectional"))
    )
    (net (code "112") (name "unconnected-(U12A-PC5-Pad45)") (class "Default")
      (node (ref "U12") (pin "45") (pinfunction "PC5_45") (pintype "bidirectional"))
    )
    (net (code "113") (name "unconnected-(U12A-PC6-Pad96)") (class "Default")
      (node (ref "U12") (pin "96") (pinfunction "PC6_96") (pintype "bidirectional"))
    )
    (net (code "114") (name "unconnected-(U12A-PC7-Pad97)") (class "Default")
      (node (ref "U12") (pin "97") (pinfunction "PC7_97") (pintype "bidirectional"))
    )
    (net (code "115") (name "unconnected-(U12A-PC8-Pad98)") (class "Default")
      (node (ref "U12") (pin "98") (pinfunction "PC8_98") (pintype "bidirectional"))
    )
    (net (code "116") (name "unconnected-(U12A-PC9-Pad99)") (class "Default")
      (node (ref "U12") (pin "99") (pinfunction "PC9_99") (pintype "bidirectional"))
    )
    (net (code "117") (name "unconnected-(U12A-PC10-Pad111)") (class "Default")
      (node (ref "U12") (pin "111") (pinfunction "PC10_111") (pintype "bidirectional"))
    )
    (net (code "118") (name "unconnected-(U12A-PC11-Pad112)") (class "Default")
      (node (ref "U12") (pin "112") (pinfunction "PC11_112") (pintype "bidirectional"))
    )
    (net (code "119") (name "unconnected-(U12A-PC12-Pad113)") (class "Default")
      (node (ref "U12") (pin "113") (pinfunction "PC12_113") (pintype "bidirectional"))
    )
    (net (code "120") (name "unconnected-(U12A-PC13-Pad7)") (class "Default")
      (node (ref "U12") (pin "7") (pinfunction "PC13_7") (pintype "bidirectional"))
    )
    (net (code "121") (name "unconnected-(U12A-PC14-OSC32_IN(PC14)-Pad8)") (class "Default")
      (node (ref "U12") (pin "8") (pinfunction "PC14-OSC32_IN(PC14)_8") (pintype "bidirectional"))
    )
    (net (code "122") (name "unconnected-(U12A-PC15-OSC32_OUT(PC15)-Pad9)") (class "Default")
      (node (ref "U12") (pin "9") (pinfunction "PC15-OSC32_OUT(PC15)_9") (pintype "bidirectional"))
    )
    (net (code "123") (name "unconnected-(U12A-PD0-Pad114)") (class "Default")
      (node (ref "U12") (pin "114") (pinfunction "PD0_114") (pintype "bidirectional"))
    )
    (net (code "124") (name "unconnected-(U12A-PD1-Pad115)") (class "Default")
      (node (ref "U12") (pin "115") (pinfunction "PD1_115") (pintype "bidirectional"))
    )
    (net (code "125") (name "unconnected-(U12A-PD2-Pad116)") (class "Default")
      (node (ref "U12") (pin "116") (pinfunction "PD2_116") (pintype "bidirectional"))
    )
    (net (code "126") (name "unconnected-(U12A-PD3-Pad117)") (class "Default")
      (node (ref "U12") (pin "117") (pinfunction "PD3_117") (pintype "bidirectional"))
    )
    (net (code "127") (name "unconnected-(U12A-PD4-Pad118)") (class "Default")
      (node (ref "U12") (pin "118") (pinfunction "PD4_118") (pintype "bidirectional"))
    )
    (net (code "128") (name "unconnected-(U12A-PD5-Pad119)") (class "Default")
      (node (ref "U12") (pin "119") (pinfunction "PD5_119") (pintype "bidirectional"))
    )
    (net (code "129") (name "unconnected-(U12A-PD6-Pad122)") (class "Default")
      (node (ref "U12") (pin "122") (pinfunction "PD6_122") (pintype "bidirectional"))
    )
    (net (code "130") (name "unconnected-(U12A-PD7-Pad123)") (class "Default")
      (node (ref "U12") (pin "123") (pinfunction "PD7_123") (pintype "bidirectional"))
    )
    (net (code "131") (name "unconnected-(U12A-PD8-Pad77)") (class "Default")
      (node (ref "U12") (pin "77") (pinfunction "PD8_77") (pintype "bidirectional"))
    )
    (net (code "132") (name "unconnected-(U12A-PD9-Pad78)") (class "Default")
      (node (ref "U12") (pin "78") (pinfunction "PD9_78") (pintype "bidirectional"))
    )
    (net (code "133") (name "unconnected-(U12A-PD10-Pad79)") (class "Default")
      (node (ref "U12") (pin "79") (pinfunction "PD10_79") (pintype "bidirectional"))
    )
    (net (code "134") (name "unconnected-(U12A-PD11-Pad80)") (class "Default")
      (node (ref "U12") (pin "80") (pinfunction "PD11_80") (pintype "bidirectional"))
    )
    (net (code "135") (name "unconnected-(U12A-PD12-Pad81)") (class "Default")
      (node (ref "U12") (pin "81") (pinfunction "PD12_81") (pintype "bidirectional"))
    )
    (net (code "136") (name "unconnected-(U12A-PD13-Pad82)") (class "Default")
      (node (ref "U12") (pin "82") (pinfunction "PD13_82") (pintype "bidirectional"))
    )
    (net (code "137") (name "unconnected-(U12A-PD14-Pad85)") (class "Default")
      (node (ref "U12") (pin "85") (pinfunction "PD14_85") (pintype "bidirectional"))
    )
    (net (code "138") (name "unconnected-(U12A-PD15-Pad86)") (class "Default")
      (node (ref "U12") (pin "86") (pinfunction "PD15_86") (pintype "bidirectional"))
    )
    (net (code "139") (name "unconnected-(U12B-BOOT0-Pad138)") (class "Default")
      (node (ref "U12") (pin "138") (pinfunction "BOOT0_138") (pintype "input"))
    )
    (net (code "140") (name "unconnected-(U12B-NRST-Pad25)") (class "Default")
      (node (ref "U12") (pin "25") (pinfunction "NRST_25") (pintype "bidirectional"))
    )
    (net (code "141") (name "unconnected-(U12B-PDR_ON-Pad143)") (class "Default")
      (node (ref "U12") (pin "143") (pinfunction "PDR_ON_143") (pintype "input"))
    )
    (net (code "142") (name "unconnected-(U12B-PE0-Pad141)") (class "Default")
      (node (ref "U12") (pin "141") (pinfunction "PE0_141") (pintype "bidirectional"))
    )
    (net (code "143") (name "unconnected-(U12B-PE1-Pad142)") (class "Default")
      (node (ref "U12") (pin "142") (pinfunction "PE1_142") (pintype "bidirectional"))
    )
    (net (code "144") (name "unconnected-(U12B-PE2-Pad1)") (class "Default")
      (node (ref "U12") (pin "1") (pinfunction "PE2_1") (pintype "bidirectional"))
    )
    (net (code "145") (name "unconnected-(U12B-PE3-Pad2)") (class "Default")
      (node (ref "U12") (pin "2") (pinfunction "PE3_2") (pintype "bidirectional"))
    )
    (net (code "146") (name "unconnected-(U12B-PE4-Pad3)") (class "Default")
      (node (ref "U12") (pin "3") (pinfunction "PE4_3") (pintype "bidirectional"))
    )
    (net (code "147") (name "unconnected-(U12B-PE5-Pad4)") (class "Default")
      (node (ref "U12") (pin "4") (pinfunction "PE5_4") (pintype "bidirectional"))
    )
    (net (code "148") (name "unconnected-(U12B-PE6-Pad5)") (class "Default")
      (node (ref "U12") (pin "5") (pinfunction "PE6_5") (pintype "bidirectional"))
    )
    (net (code "149") (name "unconnected-(U12B-PE7-Pad58)") (class "Default")
      (node (ref "U12") (pin "58") (pinfunction "PE7_58") (pintype "bidirectional"))
    )
    (net (code "150") (name "unconnected-(U12B-PE8-Pad59)") (class "Default")
      (node (ref "U12") (pin "59") (pinfunction "PE8_59") (pintype "bidirectional"))
    )
    (net (code "151") (name "unconnected-(U12B-PE9-Pad60)") (class "Default")
      (node (ref "U12") (pin "60") (pinfunction "PE9_60") (pintype "bidirectional"))
    )
    (net (code "152") (name "unconnected-(U12B-PE10-Pad63)") (class "Default")
      (node (ref "U12") (pin "63") (pinfunction "PE10_63") (pintype "bidirectional"))
    )
    (net (code "153") (name "unconnected-(U12B-PE11-Pad64)") (class "Default")
      (node (ref "U12") (pin "64") (pinfunction "PE11_64") (pintype "bidirectional"))
    )
    (net (code "154") (name "unconnected-(U12B-PE12-Pad65)") (class "Default")
      (node (ref "U12") (pin "65") (pinfunction "PE12_65") (pintype "bidirectional"))
    )
    (net (code "155") (name "unconnected-(U12B-PE13-Pad66)") (class "Default")
      (node (ref "U12") (pin "66") (pinfunction "PE13_66") (pintype "bidirectional"))
    )
    (net (code "156") (name "unconnected-(U12B-PE14-Pad67)") (class "Default")
      (node (ref "U12") (pin "67") (pinfunction "PE14_67") (pintype "bidirectional"))
    )
    (net (code "157") (name "unconnected-(U12B-PE15-Pad68)") (class "Default")
      (node (ref "U12") (pin "68") (pinfunction "PE15_68") (pintype "bidirectional"))
    )
    (net (code "158") (name "unconnected-(U12B-PF0-Pad10)") (class "Default")
      (node (ref "U12") (pin "10") (pinfunction "PF0_10") (pintype "bidirectional"))
    )
    (net (code "159") (name "unconnected-(U12B-PF1-Pad11)") (class "Default")
      (node (ref "U12") (pin "11") (pinfunction "PF1_11") (pintype "bidirectional"))
    )
    (net (code "160") (name "unconnected-(U12B-PF2-Pad12)") (class "Default")
      (node (ref "U12") (pin "12") (pinfunction "PF2_12") (pintype "bidirectional"))
    )
    (net (code "161") (name "unconnected-(U12B-PF3-Pad13)") (class "Default")
      (node (ref "U12") (pin "13") (pinfunction "PF3_13") (pintype "bidirectional"))
    )
    (net (code "162") (name "unconnected-(U12B-PF4-Pad14)") (class "Default")
      (node (ref "U12") (pin "14") (pinfunction "PF4_14") (pintype "bidirectional"))
    )
    (net (code "163") (name "unconnected-(U12B-PF5-Pad15)") (class "Default")
      (node (ref "U12") (pin "15") (pinfunction "PF5_15") (pintype "bidirectional"))
    )
    (net (code "164") (name "unconnected-(U12B-PF6-Pad18)") (class "Default")
      (node (ref "U12") (pin "18") (pinfunction "PF6_18") (pintype "bidirectional"))
    )
    (net (code "165") (name "unconnected-(U12B-PF7-Pad19)") (class "Default")
      (node (ref "U12") (pin "19") (pinfunction "PF7_19") (pintype "bidirectional"))
    )
    (net (code "166") (name "unconnected-(U12B-PF8-Pad20)") (class "Default")
      (node (ref "U12") (pin "20") (pinfunction "PF8_20") (pintype "bidirectional"))
    )
    (net (code "167") (name "unconnected-(U12B-PF9-Pad21)") (class "Default")
      (node (ref "U12") (pin "21") (pinfunction "PF9_21") (pintype "bidirectional"))
    )
    (net (code "168") (name "unconnected-(U12B-PF10-Pad22)") (class "Default")
      (node (ref "U12") (pin "22") (pinfunction "PF10_22") (pintype "bidirectional"))
    )
    (net (code "169") (name "unconnected-(U12B-PF11-Pad49)") (class "Default")
      (node (ref "U12") (pin "49") (pinfunction "PF11_49") (pintype "bidirectional"))
    )
    (net (code "170") (name "unconnected-(U12B-PF12-Pad50)") (class "Default")
      (node (ref "U12") (pin "50") (pinfunction "PF12_50") (pintype "bidirectional"))
    )
    (net (code "171") (name "unconnected-(U12B-PF13-Pad53)") (class "Default")
      (node (ref "U12") (pin "53") (pinfunction "PF13_53") (pintype "bidirectional"))
    )
    (net (code "172") (name "unconnected-(U12B-PF14-Pad54)") (class "Default")
      (node (ref "U12") (pin "54") (pinfunction "PF14_54") (pintype "bidirectional"))
    )
    (net (code "173") (name "unconnected-(U12B-PF15-Pad55)") (class "Default")
      (node (ref "U12") (pin "55") (pinfunction "PF15_55") (pintype "bidirectional"))
    )
    (net (code "174") (name "unconnected-(U12B-PG0-Pad56)") (class "Default")
      (node (ref "U12") (pin "56") (pinfunction "PG0_56") (pintype "bidirectional"))
    )
    (net (code "175") (name "unconnected-(U12B-PG1-Pad57)") (class "Default")
      (node (ref "U12") (pin "57") (pinfunction "PG1_57") (pintype "bidirectional"))
    )
    (net (code "176") (name "unconnected-(U12B-PG2-Pad87)") (class "Default")
      (node (ref "U12") (pin "87") (pinfunction "PG2_87") (pintype "bidirectional"))
    )
    (net (code "177") (name "unconnected-(U12B-PG3-Pad88)") (class "Default")
      (node (ref "U12") (pin "88") (pinfunction "PG3_88") (pintype "bidirectional"))
    )
    (net (code "178") (name "unconnected-(U12B-PG4-Pad89)") (class "Default")
      (node (ref "U12") (pin "89") (pinfunction "PG4_89") (pintype "bidirectional"))
    )
    (net (code "179") (name "unconnected-(U12B-PG5-Pad90)") (class "Default")
      (node (ref "U12") (pin "90") (pinfunction "PG5_90") (pintype "bidirectional"))
    )
    (net (code "180") (name "unconnected-(U12B-PG6-Pad91)") (class "Default")
      (node (ref "U12") (pin "91") (pinfunction "PG6_91") (pintype "bidirectional"))
    )
    (net (code "181") (name "unconnected-(U12B-PG7-Pad92)") (class "Default")
      (node (ref "U12") (pin "92") (pinfunction "PG7_92") (pintype "bidirectional"))
    )
    (net (code "182") (name "unconnected-(U12B-PG8-Pad93)") (class "Default")
      (node (ref "U12") (pin "93") (pinfunction "PG8_93") (pintype "bidirectional"))
    )
    (net (code "183") (name "unconnected-(U12B-PG9-Pad124)") (class "Default")
      (node (ref "U12") (pin "124") (pinfunction "PG9_124") (pintype "bidirectional"))
    )
    (net (code "184") (name "unconnected-(U12B-PG10-Pad125)") (class "Default")
      (node (ref "U12") (pin "125") (pinfunction "PG10_125") (pintype "bidirectional"))
    )
    (net (code "185") (name "unconnected-(U12B-PG11-Pad126)") (class "Default")
      (node (ref "U12") (pin "126") (pinfunction "PG11_126") (pintype "bidirectional"))
    )
    (net (code "186") (name "unconnected-(U12B-PG12-Pad127)") (class "Default")
      (node (ref "U12") (pin "127") (pinfunction "PG12_127") (pintype "bidirectional"))
    )
    (net (code "187") (name "unconnected-(U12B-PG13-Pad128)") (class "Default")
      (node (ref "U12") (pin "128") (pinfunction "PG13_128") (pintype "bidirectional"))
    )
    (net (code "188") (name "unconnected-(U12B-PG14-Pad129)") (class "Default")
      (node (ref "U12") (pin "129") (pinfunction "PG14_129") (pintype "bidirectional"))
    )
    (net (code "189") (name "unconnected-(U12B-PG15-Pad132)") (class "Default")
      (node (ref "U12") (pin "132") (pinfunction "PG15_132") (pintype "bidirectional"))
    )
    (net (code "190") (name "unconnected-(U12B-PH0-OSC_IN(PH0)-Pad23)") (class "Default")
      (node (ref "U12") (pin "23") (pinfunction "PH0-OSC_IN(PH0)_23") (pintype "bidirectional"))
    )
    (net (code "191") (name "unconnected-(U12B-PH1-OSC_OUT(PH1)-Pad24)") (class "Default")
      (node (ref "U12") (pin "24") (pinfunction "PH1-OSC_OUT(PH1)_24") (pintype "bidirectional"))
    )
    (net (code "192") (name "unconnected-(U12B-VCAP_1-Pad71)") (class "Default")
      (node (ref "U12") (pin "71") (pinfunction "VCAP_1_71") (pintype "power_in"))
    )
    (net (code "193") (name "unconnected-(U12B-VCAP_2-Pad106)") (class "Default")
      (node (ref "U12") (pin "106") (pinfunction "VCAP_2_106") (pintype "power_in"))
    )
    (net (code "194") (name "unconnected-(U12C-VBAT-Pad6)") (class "Default")
      (node (ref "U12") (pin "6") (pinfunction "VBAT_6") (pintype "power_in"))
    )
    (net (code "195") (name "unconnected-(U12C-VDD-Pad17)") (class "Default")
      (node (ref "U12") (pin "17") (pinfunction "VDD_17") (pintype "power_in"))
    )
    (net (code "196") (name "unconnected-(U12C-VDD-Pad30)") (class "Default")
      (node (ref "U12") (pin "30") (pinfunction "VDD_30") (pintype "power_in"))
    )
    (net (code "197") (name "unconnected-(U12C-VDD-Pad39)") (class "Default")
      (node (ref "U12") (pin "39") (pinfunction "VDD_39") (pintype "power_in"))
    )
    (net (code "198") (name "unconnected-(U12C-VDD-Pad52)") (class "Default")
      (node (ref "U12") (pin "52") (pinfunction "VDD_52") (pintype "power_in"))
    )
    (net (code "199") (name "unconnected-(U12C-VDD-Pad62)") (class "Default")
      (node (ref "U12") (pin "62") (pinfunction "VDD_62") (pintype "power_in"))
    )
    (net (code "200") (name "unconnected-(U12C-VDD-Pad72)") (class "Default")
      (node (ref "U12") (pin "72") (pinfunction "VDD_72") (pintype "power_in"))
    )
    (net (code "201") (name "unconnected-(U12C-VDD-Pad84)") (class "Default")
      (node (ref "U12") (pin "84") (pinfunction "VDD_84") (pintype "power_in"))
    )
    (net (code "202") (name "unconnected-(U12C-VDD-Pad95)") (class "Default")
      (node (ref "U12") (pin "95") (pinfunction "VDD_95") (pintype "power_in"))
    )
    (net (code "203") (name "unconnected-(U12C-VDD-Pad108)") (class "Default")
      (node (ref "U12") (pin "108") (pinfunction "VDD_108") (pintype "power_in"))
    )
    (net (code "204") (name "unconnected-(U12C-VDD-Pad121)") (class "Default")
      (node (ref "U12") (pin "121") (pinfunction "VDD_121") (pintype "power_in"))
    )
    (net (code "205") (name "unconnected-(U12C-VDD-Pad131)") (class "Default")
      (node (ref "U12") (pin "131") (pinfunction "VDD_131") (pintype "power_in"))
    )
    (net (code "206") (name "unconnected-(U12C-VDD-Pad144)") (class "Default")
      (node (ref "U12") (pin "144") (pinfunction "VDD_144") (pintype "power_in"))
    )
    (net (code "207") (name "unconnected-(U12C-VDDA-Pad33)") (class "Default")
      (node (ref "U12") (pin "33") (pinfunction "VDDA_33") (pintype "power_in"))
    )
    (net (code "208") (name "unconnected-(U12C-VREF+-Pad32)") (class "Default")
      (node (ref "U12") (pin "32") (pinfunction "VREF+_32") (pintype "power_in"))
    )
    (net (code "209") (name "unconnected-(U12C-VSS-Pad16)") (class "Default")
      (node (ref "U12") (pin "16") (pinfunction "VSS_16") (pintype "power_in"))
    )
    (net (code "210") (name "unconnected-(U12C-VSS-Pad38)") (class "Default")
      (node (ref "U12") (pin "38") (pinfunction "VSS_38") (pintype "power_in"))
    )
    (net (code "211") (name "unconnected-(U12C-VSS-Pad51)") (class "Default")
      (node (ref "U12") (pin "51") (pinfunction "VSS_51") (pintype "power_in"))
    )
    (net (code "212") (name "unconnected-(U12C-VSS-Pad61)") (class "Default")
      (node (ref "U12") (pin "61") (pinfunction "VSS_61") (pintype "power_in"))
    )
    (net (code "213") (name "unconnected-(U12C-VSS-Pad83)") (class "Default")
      (node (ref "U12") (pin "83") (pinfunction "VSS_83") (pintype "power_in"))
    )
    (net (code "214") (name "unconnected-(U12C-VSS-Pad94)") (class "Default")
      (node (ref "U12") (pin "94") (pinfunction "VSS_94") (pintype "power_in"))
    )
    (net (code "215") (name "unconnected-(U12C-VSS-Pad107)") (class "Default")
      (node (ref "U12") (pin "107") (pinfunction "VSS_107") (pintype "power_in"))
    )
    (net (code "216") (name "unconnected-(U12C-VSS-Pad120)") (class "Default")
      (node (ref "U12") (pin "120") (pinfunction "VSS_120") (pintype "power_in"))
    )
    (net (code "217") (name "unconnected-(U12C-VSS-Pad130)") (class "Default")
      (node (ref "U12") (pin "130") (pinfunction "VSS_130") (pintype "power_in"))
    )
    (net (code "218") (name "unconnected-(U12C-VSSA-Pad31)") (class "Default")
      (node (ref "U12") (pin "31") (pinfunction "VSSA_31") (pintype "power_in"))
    )
  )
)
